# voltage_sensor_v0_5.net
KiCad netlist of a schematic drawn in EAGLE
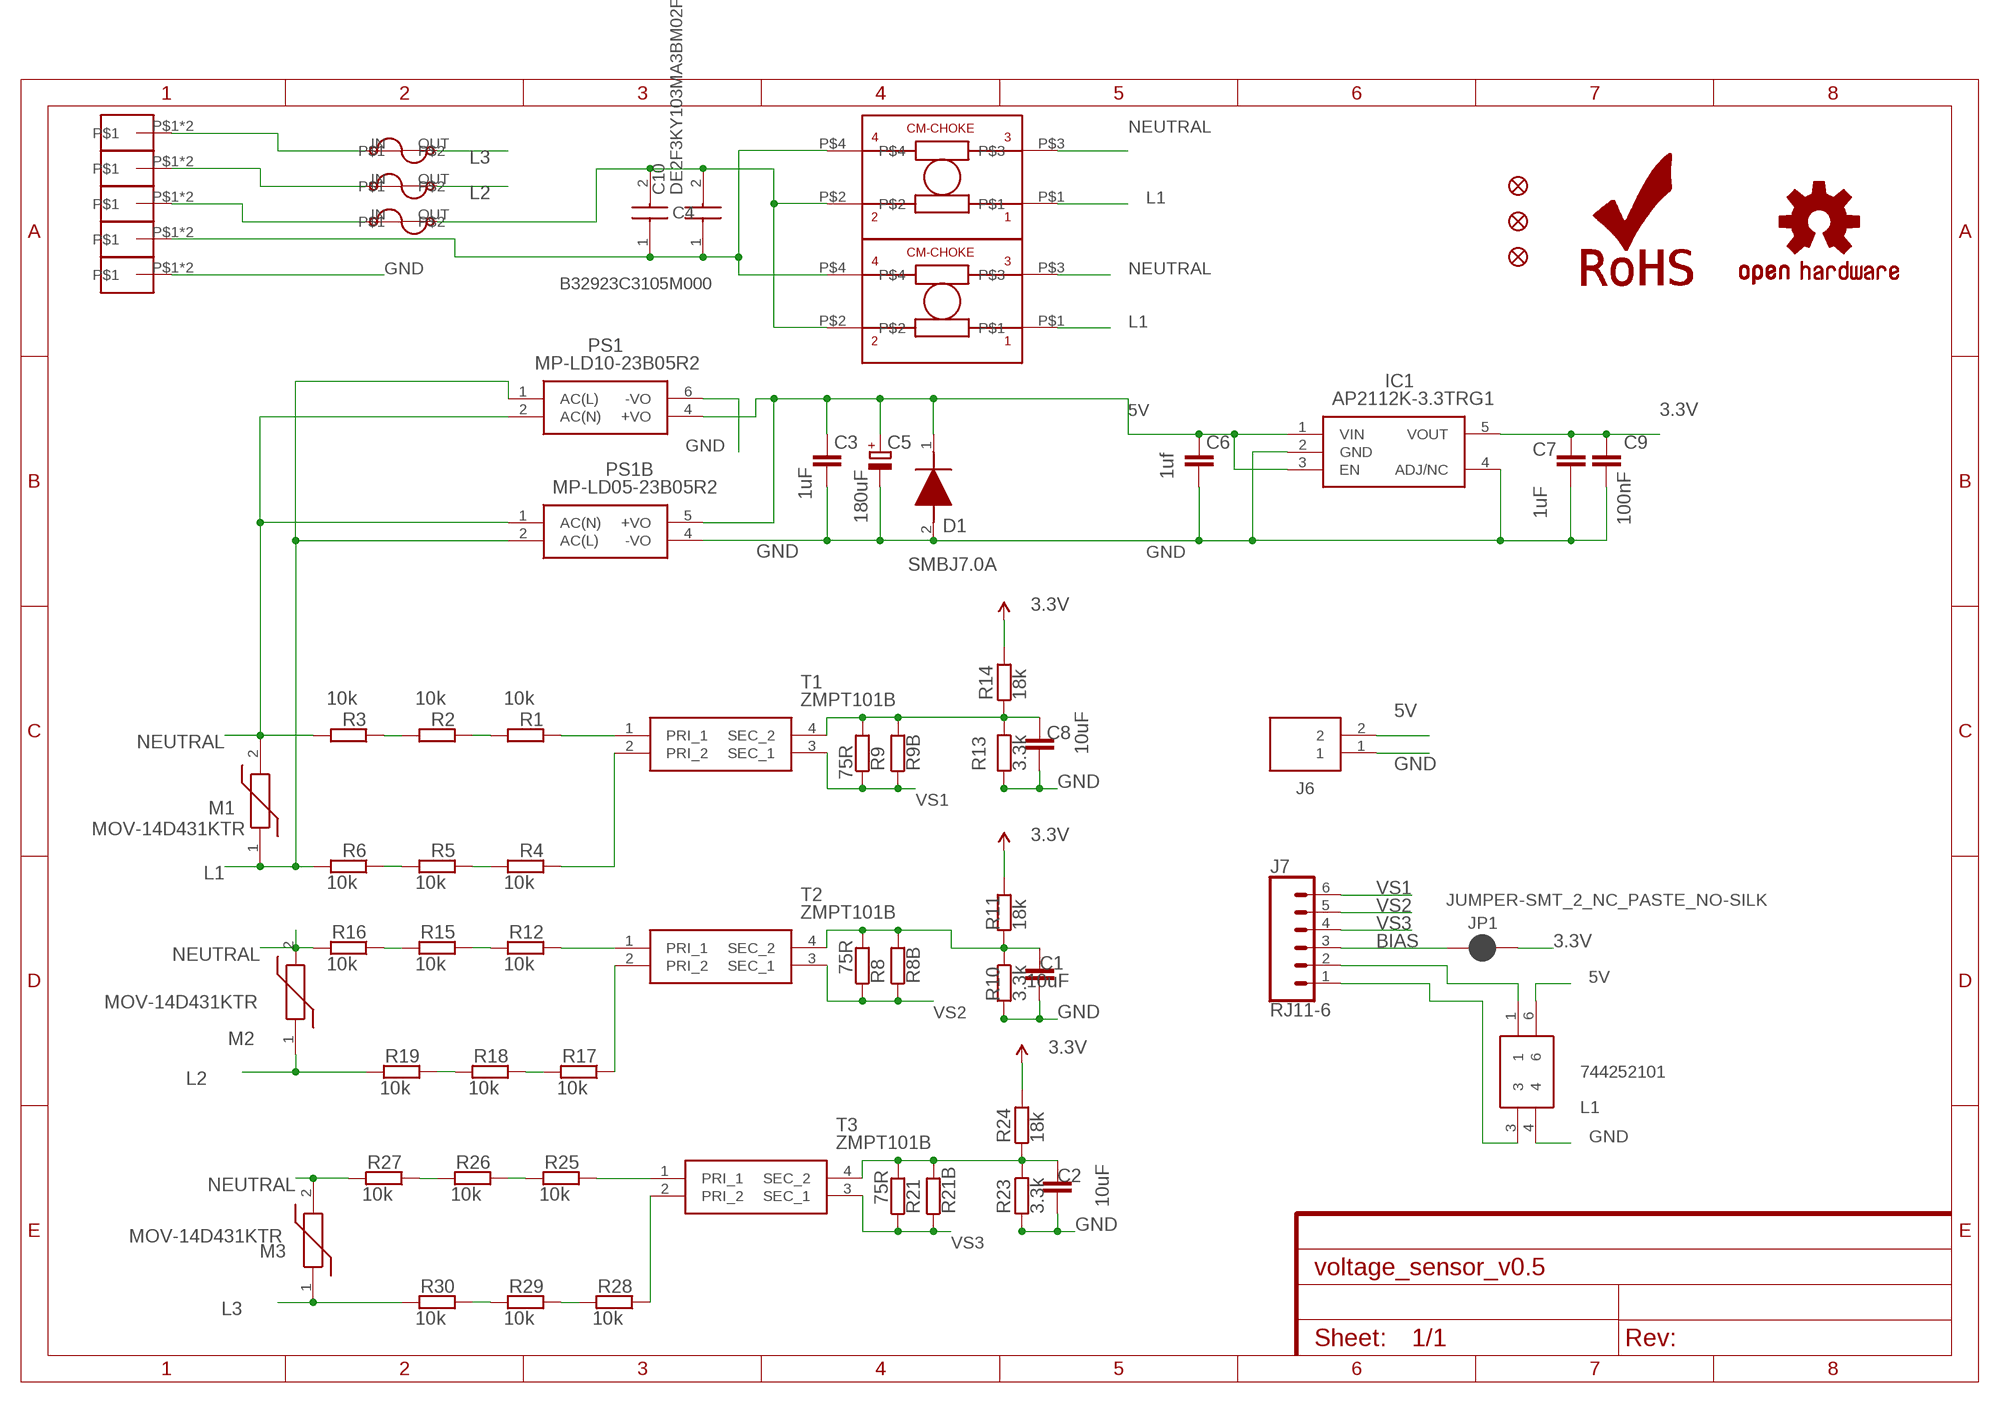
[diagram p0: schematic, sheet 1]

(export (version "E")
  (design (tool "Eeschema 10.0.6"))
  (components
    (comp (ref "C1")
      (value "10uF")
      (footprint "eagle-import:C0603")
      (libsource (lib "eagle-import") (part "C-EUC0603"))
    )
    (comp (ref "C2")
      (value "10uF")
      (footprint "eagle-import:C0603")
      (libsource (lib "eagle-import") (part "C-EUC0603"))
    )
    (comp (ref "C3")
      (value "1uF")
      (footprint "eagle-import:C0603")
      (libsource (lib "eagle-import") (part "C-EUC0603"))
    )
    (comp (ref "C4")
      (value "B32923C3105M000")
      (footprint "eagle-import:B32923C_(26.5_X_12)")
      (libsource (lib "eagle-import") (part "B32923C3105M000"))
    )
    (comp (ref "C5")
      (value "180uF")
      (footprint "eagle-import:PANASONIC_C")
      (libsource (lib "eagle-import") (part "CPOL-EUC"))
    )
    (comp (ref "C6")
      (value "1uf")
      (footprint "eagle-import:C0603")
      (libsource (lib "eagle-import") (part "C-EUC0603"))
    )
    (comp (ref "C7")
      (value "1uF")
      (footprint "eagle-import:C0603")
      (libsource (lib "eagle-import") (part "C-EUC0603"))
    )
    (comp (ref "C8")
      (value "10uF")
      (footprint "eagle-import:C0603")
      (libsource (lib "eagle-import") (part "C-EUC0603"))
    )
    (comp (ref "C9")
      (value "100nF")
      (footprint "eagle-import:C0603")
      (libsource (lib "eagle-import") (part "C-EUC0603"))
    )
    (comp (ref "C10")
      (value "DE2F3KY103MA3BM02F")
      (footprint "eagle-import:DE2F3KY103MA3BM02F")
      (fields (field (name "MOUSER_PART_NUMBER") "81-DE2F3KY103MA3BM2F"))
      (libsource (lib "eagle-import") (part "DE2F3KY103MA3BM02F"))
    )
    (comp (ref "D1")
      (value "SMBJ7.0A")
      (footprint "eagle-import:DIOM5336X244N")
      (libsource (lib "eagle-import") (part "SMBJ7.0A"))
    )
    (comp (ref "F1")
      (value "2A/250V")
      (footprint "eagle-import:BELFUSE1A")
      (libsource (lib "eagle-import") (part "BEL1AFUSE"))
    )
    (comp (ref "F2")
      (value "2A/250V")
      (footprint "eagle-import:BELFUSE1A")
      (libsource (lib "eagle-import") (part "BEL1AFUSE"))
    )
    (comp (ref "F3")
      (value "2A/250V")
      (footprint "eagle-import:BELFUSE1A")
      (libsource (lib "eagle-import") (part "BEL1AFUSE"))
    )
    (comp (ref "FD1")
      (value "FIDUCIAL1X2")
      (footprint "eagle-import:FIDUCIAL-1X2")
      (libsource (lib "eagle-import") (part "FIDUCIAL1X2"))
    )
    (comp (ref "FD2")
      (value "FIDUCIAL1X2")
      (footprint "eagle-import:FIDUCIAL-1X2")
      (libsource (lib "eagle-import") (part "FIDUCIAL1X2"))
    )
    (comp (ref "FD3")
      (value "FIDUCIAL1X2")
      (footprint "eagle-import:FIDUCIAL-1X2")
      (libsource (lib "eagle-import") (part "FIDUCIAL1X2"))
    )
    (comp (ref "IC1")
      (value "AP2112K-3.3TRG1")
      (footprint "eagle-import:SOT95P282X130-5N")
      (fields (field (name "MOUSER_PART_NUMBER") "621-AP2112K-3.3TRG1"))
      (libsource (lib "eagle-import") (part "AP2112K-3.3TRG1"))
    )
    (comp (ref "J1")
      (value "1905010")
      (footprint "eagle-import:1905010")
      (libsource (lib "eagle-import") (part "1905010"))
    )
    (comp (ref "J3")
      (value "1905010")
      (footprint "eagle-import:1905010")
      (libsource (lib "eagle-import") (part "1905010"))
    )
    (comp (ref "J4")
      (value "1905010")
      (footprint "eagle-import:1905010")
      (libsource (lib "eagle-import") (part "1905010"))
    )
    (comp (ref "J5")
      (value "1905010")
      (footprint "eagle-import:1905010")
      (libsource (lib "eagle-import") (part "1905010"))
    )
    (comp (ref "J6")
      (value "20020316-H021B01LF")
      (footprint "eagle-import:20020316H021B01LF")
      (libsource (lib "eagle-import") (part "20020316-H021B01LF"))
    )
    (comp (ref "J7")
      (value "RJ11-6")
      (footprint "eagle-import:RJ11-6")
      (libsource (lib "eagle-import") (part "RJ11-6"))
    )
    (comp (ref "JP1")
      (value "JUMPER-SMT_2_NC_PASTE_NO-SILK")
      (footprint "eagle-import:SMT-JUMPER_2_NC_PASTE_NO-SILK")
      (libsource (lib "eagle-import") (part "JUMPER-SMT_2_NC_PASTE_NO-SILK"))
    )
    (comp (ref "L1")
      (value "744252101")
      (footprint "eagle-import:744252101")
      (fields (field (name "MOUSER_PART_NUMBER") "710-744252101"))
      (libsource (lib "eagle-import") (part "744252101"))
    )
    (comp (ref "LOGO1")
      (value "ROHS_LOGO")
      (footprint "eagle-import:ROHS_LOGO_0.18_IN")
      (libsource (lib "eagle-import") (part "ROHS_LOGO"))
    )
    (comp (ref "LOGO2")
      (value "OSHW-LOGOS-COPPER")
      (footprint "eagle-import:OSHW-LOGO-S_COPPER")
      (libsource (lib "eagle-import") (part "OSHW-LOGOS-COPPER"))
    )
    (comp (ref "M1")
      (value "MOV-14D431KTR")
      (footprint "eagle-import:MOV14D431KTR")
      (fields (field (name "MOUSER_PART_NUMBER") "652-MOV-14D431KTR"))
      (libsource (lib "eagle-import") (part "MOV-14D431KTR"))
    )
    (comp (ref "M2")
      (value "MOV-14D431KTR")
      (footprint "eagle-import:MOV14D431KTR")
      (fields (field (name "MOUSER_PART_NUMBER") "652-MOV-14D431KTR"))
      (libsource (lib "eagle-import") (part "MOV-14D431KTR"))
    )
    (comp (ref "M3")
      (value "MOV-14D431KTR")
      (footprint "eagle-import:MOV14D431KTR")
      (fields (field (name "MOUSER_PART_NUMBER") "652-MOV-14D431KTR"))
      (libsource (lib "eagle-import") (part "MOV-14D431KTR"))
    )
    (comp (ref "PS1")
      (value "MP-LD10-23B05R2")
      (footprint "eagle-import:MPLD1023B12R2")
      (libsource (lib "eagle-import") (part "MP-LD10-23B12R2"))
    )
    (comp (ref "PS1B")
      (value "MP-LD05-23B05R2")
      (footprint "eagle-import:MPLD0523B03R2")
      (fields (field (name "MANUFACTURER_PART_NUMBER") "MP-LD05-23B03R2"))
      (libsource (lib "eagle-import") (part "MP-LD05-23B03R2"))
    )
    (comp (ref "R1")
      (value "10k")
      (footprint "eagle-import:R0603")
      (libsource (lib "eagle-import") (part "R-EU_R0603"))
    )
    (comp (ref "R2")
      (value "10k")
      (footprint "eagle-import:R0603")
      (libsource (lib "eagle-import") (part "R-EU_R0603"))
    )
    (comp (ref "R3")
      (value "10k")
      (footprint "eagle-import:R0603")
      (libsource (lib "eagle-import") (part "R-EU_R0603"))
    )
    (comp (ref "R4")
      (value "10k")
      (footprint "eagle-import:R0603")
      (libsource (lib "eagle-import") (part "R-EU_R0603"))
    )
    (comp (ref "R5")
      (value "10k")
      (footprint "eagle-import:R0603")
      (libsource (lib "eagle-import") (part "R-EU_R0603"))
    )
    (comp (ref "R6")
      (value "10k")
      (footprint "eagle-import:R0603")
      (libsource (lib "eagle-import") (part "R-EU_R0603"))
    )
    (comp (ref "R8")
      (value "75R")
      (footprint "eagle-import:R0603")
      (libsource (lib "eagle-import") (part "R-EU_R0603"))
    )
    (comp (ref "R8B")
      (value "R-EU_0204/7")
      (footprint "eagle-import:0204_7")
      (libsource (lib "eagle-import") (part "R-EU_0204/7"))
    )
    (comp (ref "R9")
      (value "75R")
      (footprint "eagle-import:R0603")
      (libsource (lib "eagle-import") (part "R-EU_R0603"))
    )
    (comp (ref "R9B")
      (value "R-EU_0204/7")
      (footprint "eagle-import:0204_7")
      (libsource (lib "eagle-import") (part "R-EU_0204/7"))
    )
    (comp (ref "R10")
      (value "3.3k")
      (footprint "eagle-import:R0603")
      (libsource (lib "eagle-import") (part "R-EU_R0603"))
    )
    (comp (ref "R11")
      (value "18k")
      (footprint "eagle-import:R0603")
      (libsource (lib "eagle-import") (part "R-EU_R0603"))
    )
    (comp (ref "R12")
      (value "10k")
      (footprint "eagle-import:R0603")
      (libsource (lib "eagle-import") (part "R-EU_R0603"))
    )
    (comp (ref "R13")
      (value "3.3k")
      (footprint "eagle-import:R0603")
      (libsource (lib "eagle-import") (part "R-EU_R0603"))
    )
    (comp (ref "R14")
      (value "18k")
      (footprint "eagle-import:R0603")
      (libsource (lib "eagle-import") (part "R-EU_R0603"))
    )
    (comp (ref "R15")
      (value "10k")
      (footprint "eagle-import:R0603")
      (libsource (lib "eagle-import") (part "R-EU_R0603"))
    )
    (comp (ref "R16")
      (value "10k")
      (footprint "eagle-import:R0603")
      (libsource (lib "eagle-import") (part "R-EU_R0603"))
    )
    (comp (ref "R17")
      (value "10k")
      (footprint "eagle-import:R0603")
      (libsource (lib "eagle-import") (part "R-EU_R0603"))
    )
    (comp (ref "R18")
      (value "10k")
      (footprint "eagle-import:R0603")
      (libsource (lib "eagle-import") (part "R-EU_R0603"))
    )
    (comp (ref "R19")
      (value "10k")
      (footprint "eagle-import:R0603")
      (libsource (lib "eagle-import") (part "R-EU_R0603"))
    )
    (comp (ref "R21")
      (value "75R")
      (footprint "eagle-import:R0603")
      (libsource (lib "eagle-import") (part "R-EU_R0603"))
    )
    (comp (ref "R21B")
      (value "R-EU_0204/7")
      (footprint "eagle-import:0204_7")
      (libsource (lib "eagle-import") (part "R-EU_0204/7"))
    )
    (comp (ref "R23")
      (value "3.3k")
      (footprint "eagle-import:R0603")
      (libsource (lib "eagle-import") (part "R-EU_R0603"))
    )
    (comp (ref "R24")
      (value "18k")
      (footprint "eagle-import:R0603")
      (libsource (lib "eagle-import") (part "R-EU_R0603"))
    )
    (comp (ref "R25")
      (value "10k")
      (footprint "eagle-import:R0603")
      (libsource (lib "eagle-import") (part "R-EU_R0603"))
    )
    (comp (ref "R26")
      (value "10k")
      (footprint "eagle-import:R0603")
      (libsource (lib "eagle-import") (part "R-EU_R0603"))
    )
    (comp (ref "R27")
      (value "10k")
      (footprint "eagle-import:R0603")
      (libsource (lib "eagle-import") (part "R-EU_R0603"))
    )
    (comp (ref "R28")
      (value "10k")
      (footprint "eagle-import:R0603")
      (libsource (lib "eagle-import") (part "R-EU_R0603"))
    )
    (comp (ref "R29")
      (value "10k")
      (footprint "eagle-import:R0603")
      (libsource (lib "eagle-import") (part "R-EU_R0603"))
    )
    (comp (ref "R30")
      (value "10k")
      (footprint "eagle-import:R0603")
      (libsource (lib "eagle-import") (part "R-EU_R0603"))
    )
    (comp (ref "T1")
      (value "ZMPT101B")
      (footprint "eagle-import:ZMPT101B")
      (libsource (lib "eagle-import") (part "ZMPT101B"))
    )
    (comp (ref "T2")
      (value "ZMPT101B")
      (footprint "eagle-import:ZMPT101B")
      (libsource (lib "eagle-import") (part "ZMPT101B"))
    )
    (comp (ref "T3")
      (value "ZMPT101B")
      (footprint "eagle-import:ZMPT101B")
      (libsource (lib "eagle-import") (part "ZMPT101B"))
    )
    (comp (ref "U$1")
      (value "47mH")
      (footprint "eagle-import:RN114-0.3-02-47M")
      (libsource (lib "eagle-import") (part "RN114-0.3-02-47M"))
    )
    (comp (ref "U$1B")
      (value "RN214-0.3-02-47M")
      (footprint "eagle-import:RN214-0.3-02-47M")
      (libsource (lib "eagle-import") (part "RN214-0.3-02-47M"))
    )
    (comp (ref "U$6")
      (value "1905010")
      (footprint "eagle-import:1905010")
      (libsource (lib "eagle-import") (part "1905010"))
    )
  )
  (nets
    (net (code "1") (name "/5V") (class "Default")
      (node (ref "C3") (pin "1") (pinfunction "1_1") (pintype "passive"))
      (node (ref "C5") (pin "+") (pinfunction "+_+") (pintype "passive"))
      (node (ref "C6") (pin "1") (pinfunction "1_1") (pintype "passive"))
      (node (ref "D1") (pin "1") (pinfunction "K_1") (pintype "bidirectional"))
      (node (ref "IC1") (pin "1") (pinfunction "VIN_1") (pintype "bidirectional"))
      (node (ref "IC1") (pin "3") (pinfunction "EN_3") (pintype "bidirectional"))
      (node (ref "J6") (pin "2") (pinfunction "2_2") (pintype "bidirectional"))
      (node (ref "L1") (pin "6") (pinfunction "6_6") (pintype "bidirectional"))
      (node (ref "PS1") (pin "4") (pinfunction "+VO_4") (pintype "bidirectional"))
      (node (ref "PS1B") (pin "5") (pinfunction "+VO_5") (pintype "bidirectional"))
    )
    (net (code "2") (name "/BIAS") (class "Default")
      (node (ref "J7") (pin "3") (pinfunction "3_3") (pintype "passive"))
      (node (ref "JP1") (pin "1") (pinfunction "1_1") (pintype "passive"))
    )
    (net (code "3") (name "/GND") (class "Default")
      (node (ref "C1") (pin "2") (pinfunction "2_2") (pintype "passive"))
      (node (ref "C2") (pin "2") (pinfunction "2_2") (pintype "passive"))
      (node (ref "C3") (pin "2") (pinfunction "2_2") (pintype "passive"))
      (node (ref "C5") (pin "-") (pinfunction "-_-") (pintype "passive"))
      (node (ref "C6") (pin "2") (pinfunction "2_2") (pintype "passive"))
      (node (ref "C7") (pin "2") (pinfunction "2_2") (pintype "passive"))
      (node (ref "C8") (pin "2") (pinfunction "2_2") (pintype "passive"))
      (node (ref "C9") (pin "2") (pinfunction "2_2") (pintype "passive"))
      (node (ref "D1") (pin "2") (pinfunction "A_2") (pintype "bidirectional"))
      (node (ref "IC1") (pin "2") (pinfunction "GND_2") (pintype "bidirectional"))
      (node (ref "IC1") (pin "4") (pinfunction "ADJ/NC_4") (pintype "bidirectional"))
      (node (ref "J1") (pin "P$1") (pinfunction "P$1_P$1") (pintype "bidirectional"))
      (node (ref "J1") (pin "P$2") (pinfunction "P$1_P$2") (pintype "bidirectional"))
      (node (ref "J6") (pin "1") (pinfunction "1_1") (pintype "bidirectional"))
      (node (ref "L1") (pin "4") (pinfunction "4_4") (pintype "bidirectional"))
      (node (ref "PS1") (pin "6") (pinfunction "-VO_6") (pintype "bidirectional"))
      (node (ref "PS1B") (pin "4") (pinfunction "-VO_4") (pintype "bidirectional"))
      (node (ref "R10") (pin "2") (pinfunction "2_2") (pintype "passive"))
      (node (ref "R13") (pin "2") (pinfunction "2_2") (pintype "passive"))
      (node (ref "R23") (pin "2") (pinfunction "2_2") (pintype "passive"))
    )
    (net (code "4") (name "/L1") (class "Default")
      (node (ref "M1") (pin "1") (pinfunction "1_1") (pintype "bidirectional"))
      (node (ref "PS1") (pin "1") (pinfunction "AC(L)_1") (pintype "bidirectional"))
      (node (ref "PS1B") (pin "2") (pinfunction "AC(L)_2") (pintype "bidirectional"))
      (node (ref "R6") (pin "2") (pinfunction "2_2") (pintype "passive"))
      (node (ref "U$1") (pin "P$1") (pinfunction "P$1_P$1") (pintype "bidirectional"))
      (node (ref "U$1B") (pin "P$1") (pinfunction "P$1_P$1") (pintype "bidirectional"))
    )
    (net (code "5") (name "/L2") (class "Default")
      (node (ref "F2") (pin "OUT") (pinfunction "P$1_OUT") (pintype "bidirectional"))
      (node (ref "M2") (pin "1") (pinfunction "1_1") (pintype "bidirectional"))
      (node (ref "R19") (pin "2") (pinfunction "2_2") (pintype "passive"))
    )
    (net (code "6") (name "/L3") (class "Default")
      (node (ref "F3") (pin "OUT") (pinfunction "P$1_OUT") (pintype "bidirectional"))
      (node (ref "M3") (pin "1") (pinfunction "1_1") (pintype "bidirectional"))
      (node (ref "R30") (pin "2") (pinfunction "2_2") (pintype "passive"))
    )
    (net (code "7") (name "/NEUTRAL") (class "Default")
      (node (ref "M1") (pin "2") (pinfunction "2_2") (pintype "bidirectional"))
      (node (ref "M2") (pin "2") (pinfunction "2_2") (pintype "bidirectional"))
      (node (ref "M3") (pin "2") (pinfunction "2_2") (pintype "bidirectional"))
      (node (ref "PS1") (pin "2") (pinfunction "AC(N)_2") (pintype "bidirectional"))
      (node (ref "PS1B") (pin "1") (pinfunction "AC(N)_1") (pintype "bidirectional"))
      (node (ref "R16") (pin "2") (pinfunction "2_2") (pintype "passive"))
      (node (ref "R27") (pin "2") (pinfunction "2_2") (pintype "passive"))
      (node (ref "R3") (pin "2") (pinfunction "2_2") (pintype "passive"))
      (node (ref "U$1") (pin "P$3") (pinfunction "P$3_P$3") (pintype "bidirectional"))
      (node (ref "U$1B") (pin "P$3") (pinfunction "P$3_P$3") (pintype "bidirectional"))
    )
    (net (code "8") (name "/VS1") (class "Default")
      (node (ref "J7") (pin "6") (pinfunction "6_6") (pintype "passive"))
      (node (ref "R9") (pin "1") (pinfunction "1_1") (pintype "passive"))
      (node (ref "R9B") (pin "1") (pinfunction "1_1") (pintype "passive"))
      (node (ref "T1") (pin "3") (pinfunction "SEC_1_3") (pintype "bidirectional"))
    )
    (net (code "9") (name "/VS2") (class "Default")
      (node (ref "J7") (pin "5") (pinfunction "5_5") (pintype "passive"))
      (node (ref "R8") (pin "1") (pinfunction "1_1") (pintype "passive"))
      (node (ref "R8B") (pin "1") (pinfunction "1_1") (pintype "passive"))
      (node (ref "T2") (pin "3") (pinfunction "SEC_1_3") (pintype "bidirectional"))
    )
    (net (code "10") (name "/VS3") (class "Default")
      (node (ref "J7") (pin "4") (pinfunction "4_4") (pintype "passive"))
      (node (ref "R21") (pin "1") (pinfunction "1_1") (pintype "passive"))
      (node (ref "R21B") (pin "1") (pinfunction "1_1") (pintype "passive"))
      (node (ref "T3") (pin "3") (pinfunction "SEC_1_3") (pintype "bidirectional"))
    )
    (net (code "11") (name "3.3V") (class "Default")
      (node (ref "C7") (pin "1") (pinfunction "1_1") (pintype "passive"))
      (node (ref "C9") (pin "1") (pinfunction "1_1") (pintype "passive"))
      (node (ref "IC1") (pin "5") (pinfunction "VOUT_5") (pintype "bidirectional"))
      (node (ref "JP1") (pin "2") (pinfunction "2_2") (pintype "passive"))
      (node (ref "R11") (pin "2") (pinfunction "2_2") (pintype "passive"))
      (node (ref "R14") (pin "2") (pinfunction "2_2") (pintype "passive"))
      (node (ref "R24") (pin "2") (pinfunction "2_2") (pintype "passive"))
    )
    (net (code "12") (name "Net-(C10-Pad1)") (class "Default")
      (node (ref "C10") (pin "1") (pinfunction "1_1") (pintype "bidirectional"))
      (node (ref "C4") (pin "1") (pinfunction "1_1") (pintype "bidirectional"))
      (node (ref "U$1") (pin "P$4") (pinfunction "P$4_P$4") (pintype "bidirectional"))
      (node (ref "U$1B") (pin "P$4") (pinfunction "P$4_P$4") (pintype "bidirectional"))
      (node (ref "U$6") (pin "P$1") (pinfunction "P$1_P$1") (pintype "bidirectional"))
      (node (ref "U$6") (pin "P$2") (pinfunction "P$1_P$2") (pintype "bidirectional"))
    )
    (net (code "13") (name "Net-(F1-P$1)") (class "Default")
      (node (ref "C10") (pin "2") (pinfunction "2_2") (pintype "bidirectional"))
      (node (ref "C4") (pin "2") (pinfunction "2_2") (pintype "bidirectional"))
      (node (ref "F1") (pin "OUT") (pinfunction "P$1_OUT") (pintype "bidirectional"))
      (node (ref "U$1") (pin "P$2") (pinfunction "P$2_P$2") (pintype "bidirectional"))
      (node (ref "U$1B") (pin "P$2") (pinfunction "P$2_P$2") (pintype "bidirectional"))
    )
    (net (code "14") (name "Net-(F1-P$2)") (class "Default")
      (node (ref "F1") (pin "IN") (pinfunction "P$2_IN") (pintype "bidirectional"))
      (node (ref "J3") (pin "P$1") (pinfunction "P$1_P$1") (pintype "bidirectional"))
      (node (ref "J3") (pin "P$2") (pinfunction "P$1_P$2") (pintype "bidirectional"))
    )
    (net (code "15") (name "Net-(F2-P$2)") (class "Default")
      (node (ref "F2") (pin "IN") (pinfunction "P$2_IN") (pintype "bidirectional"))
      (node (ref "J4") (pin "P$1") (pinfunction "P$1_P$1") (pintype "bidirectional"))
      (node (ref "J4") (pin "P$2") (pinfunction "P$1_P$2") (pintype "bidirectional"))
    )
    (net (code "16") (name "Net-(F3-P$2)") (class "Default")
      (node (ref "F3") (pin "IN") (pinfunction "P$2_IN") (pintype "bidirectional"))
      (node (ref "J5") (pin "P$1") (pinfunction "P$1_P$1") (pintype "bidirectional"))
      (node (ref "J5") (pin "P$2") (pinfunction "P$1_P$2") (pintype "bidirectional"))
    )
    (net (code "17") (name "Net-(J7-Pad1)") (class "Default")
      (node (ref "J7") (pin "1") (pinfunction "1_1") (pintype "passive"))
      (node (ref "L1") (pin "3") (pinfunction "3_3") (pintype "bidirectional"))
    )
    (net (code "18") (name "Net-(J7-Pad2)") (class "Default")
      (node (ref "J7") (pin "2") (pinfunction "2_2") (pintype "passive"))
      (node (ref "L1") (pin "1") (pinfunction "1_1") (pintype "bidirectional"))
    )
    (net (code "19") (name "Net-(R1-Pad2)") (class "Default")
      (node (ref "R1") (pin "2") (pinfunction "2_2") (pintype "passive"))
      (node (ref "R2") (pin "1") (pinfunction "1_1") (pintype "passive"))
    )
    (net (code "20") (name "Net-(R2-Pad2)") (class "Default")
      (node (ref "R2") (pin "2") (pinfunction "2_2") (pintype "passive"))
      (node (ref "R3") (pin "1") (pinfunction "1_1") (pintype "passive"))
    )
    (net (code "21") (name "Net-(R4-Pad2)") (class "Default")
      (node (ref "R4") (pin "2") (pinfunction "2_2") (pintype "passive"))
      (node (ref "R5") (pin "1") (pinfunction "1_1") (pintype "passive"))
    )
    (net (code "22") (name "Net-(R5-Pad2)") (class "Default")
      (node (ref "R5") (pin "2") (pinfunction "2_2") (pintype "passive"))
      (node (ref "R6") (pin "1") (pinfunction "1_1") (pintype "passive"))
    )
    (net (code "23") (name "Net-(R12-Pad2)") (class "Default")
      (node (ref "R12") (pin "2") (pinfunction "2_2") (pintype "passive"))
      (node (ref "R15") (pin "1") (pinfunction "1_1") (pintype "passive"))
    )
    (net (code "24") (name "Net-(R15-Pad2)") (class "Default")
      (node (ref "R15") (pin "2") (pinfunction "2_2") (pintype "passive"))
      (node (ref "R16") (pin "1") (pinfunction "1_1") (pintype "passive"))
    )
    (net (code "25") (name "Net-(R17-Pad2)") (class "Default")
      (node (ref "R17") (pin "2") (pinfunction "2_2") (pintype "passive"))
      (node (ref "R18") (pin "1") (pinfunction "1_1") (pintype "passive"))
    )
    (net (code "26") (name "Net-(R18-Pad2)") (class "Default")
      (node (ref "R18") (pin "2") (pinfunction "2_2") (pintype "passive"))
      (node (ref "R19") (pin "1") (pinfunction "1_1") (pintype "passive"))
    )
    (net (code "27") (name "Net-(R25-Pad2)") (class "Default")
      (node (ref "R25") (pin "2") (pinfunction "2_2") (pintype "passive"))
      (node (ref "R26") (pin "1") (pinfunction "1_1") (pintype "passive"))
    )
    (net (code "28") (name "Net-(R26-Pad2)") (class "Default")
      (node (ref "R26") (pin "2") (pinfunction "2_2") (pintype "passive"))
      (node (ref "R27") (pin "1") (pinfunction "1_1") (pintype "passive"))
    )
    (net (code "29") (name "Net-(R28-Pad2)") (class "Default")
      (node (ref "R28") (pin "2") (pinfunction "2_2") (pintype "passive"))
      (node (ref "R29") (pin "1") (pinfunction "1_1") (pintype "passive"))
    )
    (net (code "30") (name "Net-(R29-Pad2)") (class "Default")
      (node (ref "R29") (pin "2") (pinfunction "2_2") (pintype "passive"))
      (node (ref "R30") (pin "1") (pinfunction "1_1") (pintype "passive"))
    )
    (net (code "31") (name "Net-(T1-PRI_1)") (class "Default")
      (node (ref "R1") (pin "1") (pinfunction "1_1") (pintype "passive"))
      (node (ref "T1") (pin "1") (pinfunction "PRI_1_1") (pintype "bidirectional"))
    )
    (net (code "32") (name "Net-(T1-PRI_2)") (class "Default")
      (node (ref "R4") (pin "1") (pinfunction "1_1") (pintype "passive"))
      (node (ref "T1") (pin "2") (pinfunction "PRI_2_2") (pintype "bidirectional"))
    )
    (net (code "33") (name "Net-(T1-SEC_2)") (class "Default")
      (node (ref "C8") (pin "1") (pinfunction "1_1") (pintype "passive"))
      (node (ref "R13") (pin "1") (pinfunction "1_1") (pintype "passive"))
      (node (ref "R14") (pin "1") (pinfunction "1_1") (pintype "passive"))
      (node (ref "R9") (pin "2") (pinfunction "2_2") (pintype "passive"))
      (node (ref "R9B") (pin "2") (pinfunction "2_2") (pintype "passive"))
      (node (ref "T1") (pin "4") (pinfunction "SEC_2_4") (pintype "bidirectional"))
    )
    (net (code "34") (name "Net-(T2-PRI_1)") (class "Default")
      (node (ref "R12") (pin "1") (pinfunction "1_1") (pintype "passive"))
      (node (ref "T2") (pin "1") (pinfunction "PRI_1_1") (pintype "bidirectional"))
    )
    (net (code "35") (name "Net-(T2-PRI_2)") (class "Default")
      (node (ref "R17") (pin "1") (pinfunction "1_1") (pintype "passive"))
      (node (ref "T2") (pin "2") (pinfunction "PRI_2_2") (pintype "bidirectional"))
    )
    (net (code "36") (name "Net-(T2-SEC_2)") (class "Default")
      (node (ref "C1") (pin "1") (pinfunction "1_1") (pintype "passive"))
      (node (ref "R10") (pin "1") (pinfunction "1_1") (pintype "passive"))
      (node (ref "R11") (pin "1") (pinfunction "1_1") (pintype "passive"))
      (node (ref "R8") (pin "2") (pinfunction "2_2") (pintype "passive"))
      (node (ref "R8B") (pin "2") (pinfunction "2_2") (pintype "passive"))
      (node (ref "T2") (pin "4") (pinfunction "SEC_2_4") (pintype "bidirectional"))
    )
    (net (code "37") (name "Net-(T3-PRI_1)") (class "Default")
      (node (ref "R25") (pin "1") (pinfunction "1_1") (pintype "passive"))
      (node (ref "T3") (pin "1") (pinfunction "PRI_1_1") (pintype "bidirectional"))
    )
    (net (code "38") (name "Net-(T3-PRI_2)") (class "Default")
      (node (ref "R28") (pin "1") (pinfunction "1_1") (pintype "passive"))
      (node (ref "T3") (pin "2") (pinfunction "PRI_2_2") (pintype "bidirectional"))
    )
    (net (code "39") (name "Net-(T3-SEC_2)") (class "Default")
      (node (ref "C2") (pin "1") (pinfunction "1_1") (pintype "passive"))
      (node (ref "R21") (pin "2") (pinfunction "2_2") (pintype "passive"))
      (node (ref "R21B") (pin "2") (pinfunction "2_2") (pintype "passive"))
      (node (ref "R23") (pin "1") (pinfunction "1_1") (pintype "passive"))
      (node (ref "R24") (pin "1") (pinfunction "1_1") (pintype "passive"))
      (node (ref "T3") (pin "4") (pinfunction "SEC_2_4") (pintype "bidirectional"))
    )
  )
)
